# SourceFollower_TSFP-4-1_Modular.net
KiCad netlist of a schematic drawn in Altium Designer
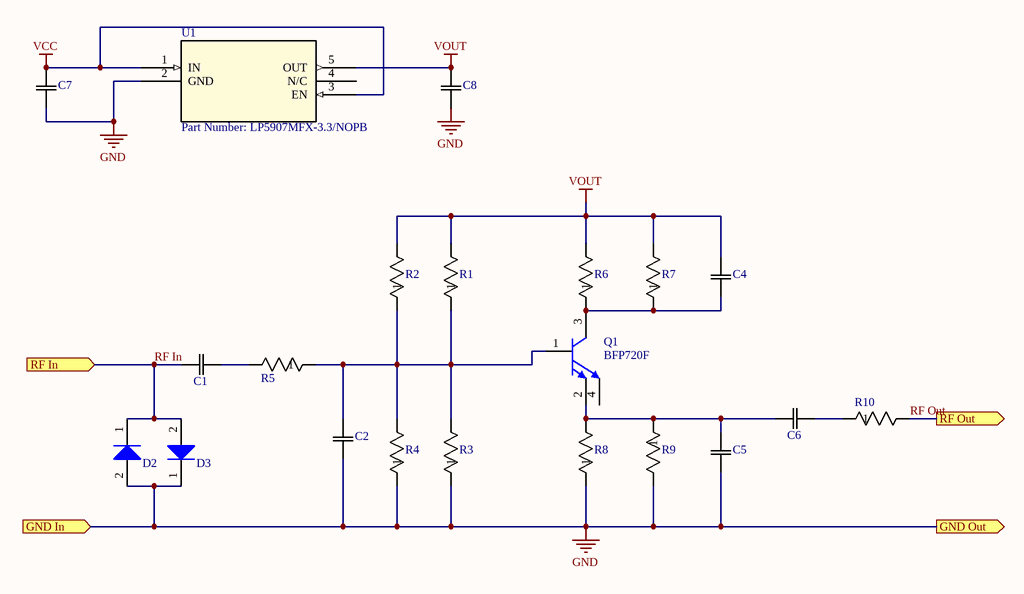
[diagram p0: SourceFollower_TSFP-4-1_Modular.SchDoc]

(export (version "E")
  (design (tool "Eeschema 10.0.6"))
  (components
    (comp (ref "C1")
      (value "Part Number: C0201C270J3GACTU")
      (footprint "C0201")
      (description "No Description Available")
      (fields
        (field (name "MANUFACTURER_PART_NUMBER") "C0201C270J3GACTU")
        (field (name "COPYRIGHT") "Copyright (C) 2018 Accelerated Designs. All rights reserved")
      )
      (libsource (lib "0201Capacitor_Yageo") (part "C0201C270J3GACTU"))
    )
    (comp (ref "C2")
      (value "Part Number: C0201C270J3GACTU")
      (footprint "C0201")
      (description "No Description Available")
      (fields
        (field (name "MANUFACTURER_PART_NUMBER") "C0201C270J3GACTU")
        (field (name "COPYRIGHT") "Copyright (C) 2018 Accelerated Designs. All rights reserved")
      )
      (libsource (lib "0201Capacitor_Yageo") (part "C0201C270J3GACTU"))
    )
    (comp (ref "C4")
      (value "Part Number: C0201C270J3GACTU")
      (footprint "C0201")
      (description "No Description Available")
      (fields
        (field (name "MANUFACTURER_PART_NUMBER") "C0201C270J3GACTU")
        (field (name "COPYRIGHT") "Copyright (C) 2018 Accelerated Designs. All rights reserved")
      )
      (libsource (lib "0201Capacitor_Yageo") (part "C0201C270J3GACTU"))
    )
    (comp (ref "C5")
      (value "Part Number: C0201C270J3GACTU")
      (footprint "C0201")
      (description "No Description Available")
      (fields
        (field (name "MANUFACTURER_PART_NUMBER") "C0201C270J3GACTU")
        (field (name "COPYRIGHT") "Copyright (C) 2018 Accelerated Designs. All rights reserved")
      )
      (libsource (lib "0201Capacitor_Yageo") (part "C0201C270J3GACTU"))
    )
    (comp (ref "C6")
      (value "Part Number: C0201C270J3GACTU")
      (footprint "C0201")
      (description "No Description Available")
      (fields
        (field (name "MANUFACTURER_PART_NUMBER") "C0201C270J3GACTU")
        (field (name "COPYRIGHT") "Copyright (C) 2018 Accelerated Designs. All rights reserved")
      )
      (libsource (lib "0201Capacitor_Yageo") (part "C0201C270J3GACTU"))
    )
    (comp (ref "C7")
      (value "Part Number: CC0402KRX7R6BB104")
      (footprint "YAG_CC0402")
      (description "No Description Available")
      (fields
        (field (name "MANUFACTURER_PART_NUMBER") "CC0402KRX7R6BB104")
        (field (name "COPYRIGHT") "Copyright (C) 2018 Accelerated Designs. All rights reserved")
      )
      (libsource (lib "0402Capacitor_Yageo") (part "CC0402KRX7R6BB10"))
    )
    (comp (ref "C8")
      (value "Part Number: CC0402KRX7R6BB104")
      (footprint "YAG_CC0402")
      (description "No Description Available")
      (fields
        (field (name "MANUFACTURER_PART_NUMBER") "CC0402KRX7R6BB104")
        (field (name "COPYRIGHT") "Copyright (C) 2018 Accelerated Designs. All rights reserved")
      )
      (libsource (lib "0402Capacitor_Yageo") (part "CC0402KRX7R6BB10"))
    )
    (comp (ref "D2")
      (value "BAT15-03W")
      (footprint "INF-SOD323_V")
      (description "Single Silicon Schottky Diode, 110 mA IF Max, SOD32, Green")
      (fields (field (name "MANUFACTURER") "Infineon"))
      (libsource (lib "Infineon_RFSchottkyDiode_SOD323") (part "BAT15-03W"))
    )
    (comp (ref "D3")
      (value "BAT15-03W")
      (footprint "INF-SOD323_V")
      (description "Single Silicon Schottky Diode, 110 mA IF Max, SOD32, Green")
      (fields (field (name "MANUFACTURER") "Infineon"))
      (libsource (lib "Infineon_RFSchottkyDiode_SOD323") (part "BAT15-03W"))
    )
    (comp (ref "Q1")
      (value "BFP720F")
      (footprint "INF-TSFP-4-1_V")
      (fields (field (name "MANUFACTURER") "Infineon"))
      (libsource (lib "Infineon_RFBJT_TSFP-4-1") (part "BFP720F"))
    )
    (comp (ref "R1")
      (value "Part Number: RC0201FR-0718KL")
      (footprint "RES_RC0201_P6XP3")
      (description "No Description Available")
      (fields
        (field (name "MANUFACTURER_PART_NUMBER") "RC0201FR-0718KL")
        (field (name "COPYRIGHT") "Copyright (C) 2018 Accelerated Designs. All rights reserved")
      )
      (libsource (lib "0201Resistor_Yageo") (part "RC0201FR-0718KL"))
    )
    (comp (ref "R2")
      (value "Part Number: RC0201FR-0718KL")
      (footprint "RES_RC0201_P6XP3")
      (description "No Description Available")
      (fields
        (field (name "MANUFACTURER_PART_NUMBER") "RC0201FR-0718KL")
        (field (name "COPYRIGHT") "Copyright (C) 2018 Accelerated Designs. All rights reserved")
      )
      (libsource (lib "0201Resistor_Yageo") (part "RC0201FR-0718KL"))
    )
    (comp (ref "R3")
      (value "Part Number: RC0201FR-0718KL")
      (footprint "RES_RC0201_P6XP3")
      (description "No Description Available")
      (fields
        (field (name "MANUFACTURER_PART_NUMBER") "RC0201FR-0718KL")
        (field (name "COPYRIGHT") "Copyright (C) 2018 Accelerated Designs. All rights reserved")
      )
      (libsource (lib "0201Resistor_Yageo") (part "RC0201FR-0718KL"))
    )
    (comp (ref "R4")
      (value "Part Number: RC0201FR-0718KL")
      (footprint "RES_RC0201_P6XP3")
      (description "No Description Available")
      (fields
        (field (name "MANUFACTURER_PART_NUMBER") "RC0201FR-0718KL")
        (field (name "COPYRIGHT") "Copyright (C) 2018 Accelerated Designs. All rights reserved")
      )
      (libsource (lib "0201Resistor_Yageo") (part "RC0201FR-0718KL"))
    )
    (comp (ref "R5")
      (value "Part Number: RC0201FR-0718KL")
      (footprint "RES_RC0201_P6XP3")
      (description "No Description Available")
      (fields
        (field (name "MANUFACTURER_PART_NUMBER") "RC0201FR-0718KL")
        (field (name "COPYRIGHT") "Copyright (C) 2018 Accelerated Designs. All rights reserved")
      )
      (libsource (lib "0201Resistor_Yageo") (part "RC0201FR-0718KL"))
    )
    (comp (ref "R6")
      (value "Part Number: RC0201FR-0718KL")
      (footprint "RES_RC0201_P6XP3")
      (description "No Description Available")
      (fields
        (field (name "MANUFACTURER_PART_NUMBER") "RC0201FR-0718KL")
        (field (name "COPYRIGHT") "Copyright (C) 2018 Accelerated Designs. All rights reserved")
      )
      (libsource (lib "0201Resistor_Yageo") (part "RC0201FR-0718KL"))
    )
    (comp (ref "R7")
      (value "Part Number: RC0201FR-0718KL")
      (footprint "RES_RC0201_P6XP3")
      (description "No Description Available")
      (fields
        (field (name "MANUFACTURER_PART_NUMBER") "RC0201FR-0718KL")
        (field (name "COPYRIGHT") "Copyright (C) 2018 Accelerated Designs. All rights reserved")
      )
      (libsource (lib "0201Resistor_Yageo") (part "RC0201FR-0718KL"))
    )
    (comp (ref "R8")
      (value "Part Number: RC0201FR-0718KL")
      (footprint "RES_RC0201_P6XP3")
      (description "No Description Available")
      (fields
        (field (name "MANUFACTURER_PART_NUMBER") "RC0201FR-0718KL")
        (field (name "COPYRIGHT") "Copyright (C) 2018 Accelerated Designs. All rights reserved")
      )
      (libsource (lib "0201Resistor_Yageo") (part "RC0201FR-0718KL"))
    )
    (comp (ref "R9")
      (value "Part Number: RC0201FR-0718KL")
      (footprint "RES_RC0201_P6XP3")
      (description "No Description Available")
      (fields
        (field (name "MANUFACTURER_PART_NUMBER") "RC0201FR-0718KL")
        (field (name "COPYRIGHT") "Copyright (C) 2018 Accelerated Designs. All rights reserved")
      )
      (libsource (lib "0201Resistor_Yageo") (part "RC0201FR-0718KL"))
    )
    (comp (ref "R10")
      (value "Part Number: RC0201FR-0718KL")
      (footprint "RES_RC0201_P6XP3")
      (description "No Description Available")
      (fields
        (field (name "MANUFACTURER_PART_NUMBER") "RC0201FR-0718KL")
        (field (name "COPYRIGHT") "Copyright (C) 2018 Accelerated Designs. All rights reserved")
      )
      (libsource (lib "0201Resistor_Yageo") (part "RC0201FR-0718KL"))
    )
    (comp (ref "U1")
      (value "Part Number: LP5907MFX-3.3/NOPB")
      (footprint "DBV5")
      (description "No Description Available")
      (fields
        (field (name "MANUFACTURER_PART_NUMBER") "LP5907MFX-3.3/NOPB")
        (field (name "COPYRIGHT") "Copyright (C) 2018 Accelerated Designs. All rights reserved")
      )
      (libsource (lib "TI_LDO_3V3_SOT325") (part "LP5907MFX-3.3/NO"))
    )
  )
  (nets
    (net (code "1") (name "/RF In") (class "Default")
      (node (ref "C1") (pin "1") (pinfunction "1_1") (pintype "passive"))
      (node (ref "D2") (pin "1") (pinfunction "K_1") (pintype "passive"))
      (node (ref "D3") (pin "2") (pinfunction "A_2") (pintype "passive"))
    )
    (net (code "2") (name "/RF Out") (class "Default")
      (node (ref "R10") (pin "2") (pinfunction "2_2") (pintype "passive"))
    )
    (net (code "3") (name "GND") (class "Default")
      (node (ref "C2") (pin "1") (pinfunction "1_1") (pintype "passive"))
      (node (ref "C5") (pin "1") (pinfunction "1_1") (pintype "passive"))
      (node (ref "C7") (pin "1") (pinfunction "1_1") (pintype "passive"))
      (node (ref "C8") (pin "1") (pinfunction "1_1") (pintype "passive"))
      (node (ref "D2") (pin "2") (pinfunction "A_2") (pintype "passive"))
      (node (ref "D3") (pin "1") (pinfunction "K_1") (pintype "passive"))
      (node (ref "R3") (pin "1") (pinfunction "1_1") (pintype "passive"))
      (node (ref "R4") (pin "1") (pinfunction "1_1") (pintype "passive"))
      (node (ref "R8") (pin "1") (pinfunction "1_1") (pintype "passive"))
      (node (ref "R9") (pin "2") (pinfunction "2_2") (pintype "passive"))
      (node (ref "U1") (pin "2") (pinfunction "GND_2") (pintype "power_in"))
    )
    (net (code "4") (name "Net-(C1-Pad2)") (class "Default")
      (node (ref "C1") (pin "2") (pinfunction "2_2") (pintype "passive"))
      (node (ref "R5") (pin "2") (pinfunction "2_2") (pintype "passive"))
    )
    (net (code "5") (name "Net-(C5-Pad2)") (class "Default")
      (node (ref "C5") (pin "2") (pinfunction "2_2") (pintype "passive"))
      (node (ref "C6") (pin "2") (pinfunction "2_2") (pintype "passive"))
      (node (ref "Q1") (pin "2") (pinfunction "E_2") (pintype "passive"))
      (node (ref "R8") (pin "2") (pinfunction "2_2") (pintype "passive"))
      (node (ref "R9") (pin "1") (pinfunction "1_1") (pintype "passive"))
    )
    (net (code "6") (name "Net-(C6-Pad1)") (class "Default")
      (node (ref "C6") (pin "1") (pinfunction "1_1") (pintype "passive"))
      (node (ref "R10") (pin "1") (pinfunction "1_1") (pintype "passive"))
    )
    (net (code "7") (name "Net-(Q1-B)") (class "Default")
      (node (ref "C2") (pin "2") (pinfunction "2_2") (pintype "passive"))
      (node (ref "Q1") (pin "1") (pinfunction "B_1") (pintype "passive"))
      (node (ref "R1") (pin "1") (pinfunction "1_1") (pintype "passive"))
      (node (ref "R2") (pin "1") (pinfunction "1_1") (pintype "passive"))
      (node (ref "R3") (pin "2") (pinfunction "2_2") (pintype "passive"))
      (node (ref "R4") (pin "2") (pinfunction "2_2") (pintype "passive"))
      (node (ref "R5") (pin "1") (pinfunction "1_1") (pintype "passive"))
    )
    (net (code "8") (name "Net-(Q1-C)") (class "Default")
      (node (ref "C4") (pin "1") (pinfunction "1_1") (pintype "passive"))
      (node (ref "Q1") (pin "3") (pinfunction "C_3") (pintype "passive"))
      (node (ref "R6") (pin "1") (pinfunction "1_1") (pintype "passive"))
      (node (ref "R7") (pin "1") (pinfunction "1_1") (pintype "passive"))
    )
    (net (code "9") (name "VCC") (class "Default")
      (node (ref "C7") (pin "2") (pinfunction "2_2") (pintype "passive"))
      (node (ref "U1") (pin "1") (pinfunction "IN_1") (pintype "input"))
      (node (ref "U1") (pin "3") (pinfunction "EN_3") (pintype "input"))
    )
    (net (code "10") (name "VOUT") (class "Default")
      (node (ref "C4") (pin "2") (pinfunction "2_2") (pintype "passive"))
      (node (ref "C8") (pin "2") (pinfunction "2_2") (pintype "passive"))
      (node (ref "R1") (pin "2") (pinfunction "2_2") (pintype "passive"))
      (node (ref "R2") (pin "2") (pinfunction "2_2") (pintype "passive"))
      (node (ref "R6") (pin "2") (pinfunction "2_2") (pintype "passive"))
      (node (ref "R7") (pin "2") (pinfunction "2_2") (pintype "passive"))
      (node (ref "U1") (pin "5") (pinfunction "OUT_5") (pintype "output"))
    )
    (net (code "11") (name "unconnected-(Q1-E-Pad4)") (class "Default")
      (node (ref "Q1") (pin "4") (pinfunction "E_4") (pintype "passive"))
    )
    (net (code "12") (name "unconnected-(U1-N{slash}C-Pad4)") (class "Default")
      (node (ref "U1") (pin "4") (pinfunction "N/C_4") (pintype "passive"))
    )
  )
)
